# RSheet1.net
KiCad netlist of a schematic drawn in Altium Designer
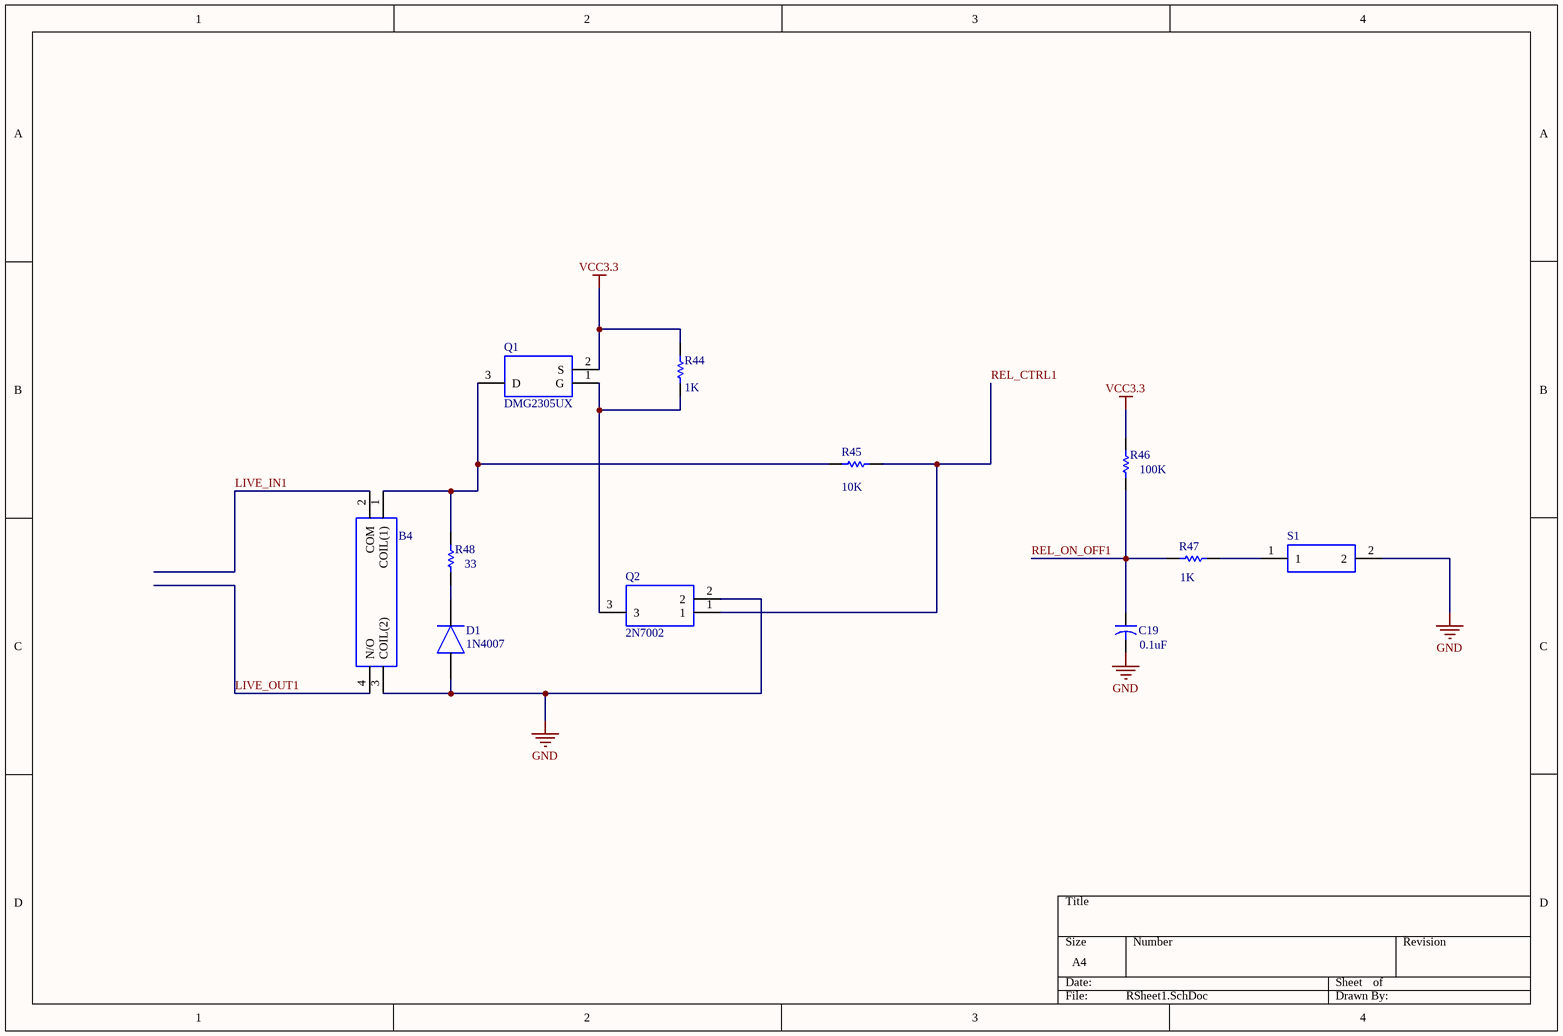
[diagram p0: RSheet1.SchDoc]

(export (version "E")
  (design (tool "Eeschema 10.0.6"))
  (components
    (comp (ref "B4")
      (value "HF3FA_005-HTF")
      (footprint "HF3FA005HTF:HF3FA005HTF")
      (description "Subminiature high power relay. 10A 5V.")
      (fields (field (name "MANUFACTURER_PART_NUMBER") "HF3FA/005-HTF"))
      (libsource (lib "HF3FA_005-HTF") (part "HF3FA_005-HTF"))
    )
    (comp (ref "C19")
      (value "0.1uF")
      (footprint "RESC0603X26N:RESC0603X26N")
      (description "Capacitor")
      (fields (field (name "Comment") "Cap2") (field (name "PUBLISHER") "Altium Limited"))
      (libsource (lib "Miscellaneous Devices") (part "Cap2"))
    )
    (comp (ref "D1")
      (value "1N4007")
      (footprint "DIOAD1408W86L464D236:DIOAD1408W86L464D236")
      (description "Diode Standard 1A 1000V 1Vf DO41 Diodes Inc 1N4007-T, Switching Diode, 1000V 1A, 2-Pin DO-41")
      (fields (field (name "RS PART NUMBER") "7384724P") (field (name "MANUFACTURER_PART_NUMBER") "1N4007-T"))
      (libsource (lib "1N4007-T") (part "1N4007-T"))
    )
    (comp (ref "Q1")
      (value "DMG2305UX")
      (footprint "SOT96P240X100-3N:SOT96P240X100-3N")
      (fields
        (field (name "RS PART NUMBER") "1219640")
        (field (name "MANUFACTURER_PART_NUMBER") "DMG2305UX-7")
      )
      (libsource (lib "DMG2305UX-7") (part "DMG2305UX-7"))
    )
    (comp (ref "Q2")
      (value "2N7002")
      (footprint "SOT95P230X110-3N:SOT95P230X110-3N")
      (fields
        (field (name "RS PART NUMBER") "1125526")
        (field (name "MANUFACTURER_PART_NUMBER") "2N7002,215")
      )
      (libsource (lib "2N7002_215") (part "2N7002_215"))
    )
    (comp (ref "R44")
      (value "1K")
      (footprint "AXIAL-0.3")
      (description "Resistor")
      (fields (field (name "Comment") "Res1") (field (name "PUBLISHER") "Altium Limited"))
      (libsource (lib "Miscellaneous Devices") (part "Res1"))
    )
    (comp (ref "R45")
      (value "10K")
      (footprint "AXIAL-0.3")
      (description "Resistor")
      (fields (field (name "Comment") "Res1") (field (name "PUBLISHER") "Altium Limited"))
      (libsource (lib "Miscellaneous Devices") (part "Res1"))
    )
    (comp (ref "R46")
      (value "100K")
      (footprint "RESC0603X26N:RESC0603X26N")
      (description "Resistor")
      (fields (field (name "Comment") "Res1") (field (name "PUBLISHER") "Altium Limited"))
      (libsource (lib "Miscellaneous Devices") (part "Res1"))
    )
    (comp (ref "R47")
      (value "1K")
      (footprint "RESC0603X26N:RESC0603X26N")
      (description "Resistor")
      (fields (field (name "Comment") "Res1") (field (name "PUBLISHER") "Altium Limited"))
      (libsource (lib "Miscellaneous Devices") (part "Res1"))
    )
    (comp (ref "R48")
      (value "33")
      (footprint "AXIAL-0.3")
      (description "Resistor")
      (fields (field (name "PUBLISHER") "Altium Limited"))
      (libsource (lib "Miscellaneous Devices") (part "Res1"))
    )
    (comp (ref "S1")
      (value "TL3330AF260QG")
      (footprint "SMD & J-Bend Tact Switch WS-TASV:434121043836")
      (description "Tactile Switches 50mA@12VDC 260g OF Silver contacts")
      (libsource (lib "TL3330AF260QG") (part "TL3330AF260QG"))
    )
  )
  (nets
    (net (code "1") (name "/LIVE_IN1") (class "Default")
      (node (ref "B4") (pin "2") (pinfunction "COM_2") (pintype "passive"))
    )
    (net (code "2") (name "/LIVE_OUT1") (class "Default")
      (node (ref "B4") (pin "4") (pinfunction "N/O_4") (pintype "passive"))
    )
    (net (code "3") (name "/REL_CTRL1") (class "Default")
      (node (ref "Q2") (pin "1") (pinfunction "1_1") (pintype "passive"))
      (node (ref "R45") (pin "2") (pinfunction "2_2") (pintype "passive"))
    )
    (net (code "4") (name "/REL_ON_OFF1") (class "Default")
      (node (ref "C19") (pin "1") (pinfunction "1_1") (pintype "passive"))
      (node (ref "R46") (pin "1") (pinfunction "1_1") (pintype "passive"))
      (node (ref "R47") (pin "1") (pinfunction "1_1") (pintype "passive"))
    )
    (net (code "5") (name "GND") (class "Default")
      (node (ref "B4") (pin "3") (pinfunction "COIL(2)_3") (pintype "passive"))
      (node (ref "C19") (pin "2") (pinfunction "2_2") (pintype "passive"))
      (node (ref "D1") (pin "2") (pinfunction "A_2") (pintype "passive"))
      (node (ref "Q2") (pin "2") (pinfunction "2_2") (pintype "passive"))
      (node (ref "S1") (pin "2") (pinfunction "2_2") (pintype "passive"))
    )
    (net (code "6") (name "Net-(B4-COIL(1))") (class "Default")
      (node (ref "B4") (pin "1") (pinfunction "COIL(1)_1") (pintype "passive"))
      (node (ref "Q1") (pin "3") (pinfunction "D_3") (pintype "passive"))
      (node (ref "R45") (pin "1") (pinfunction "1_1") (pintype "passive"))
      (node (ref "R48") (pin "2") (pinfunction "2_2") (pintype "passive"))
    )
    (net (code "7") (name "Net-(D1-K)") (class "Default")
      (node (ref "D1") (pin "1") (pinfunction "K_1") (pintype "passive"))
      (node (ref "R48") (pin "1") (pinfunction "1_1") (pintype "passive"))
    )
    (net (code "8") (name "Net-(Q1-G)") (class "Default")
      (node (ref "Q1") (pin "1") (pinfunction "G_1") (pintype "passive"))
      (node (ref "Q2") (pin "3") (pinfunction "3_3") (pintype "passive"))
      (node (ref "R44") (pin "1") (pinfunction "1_1") (pintype "passive"))
    )
    (net (code "9") (name "Net-(R47-Pad2)") (class "Default")
      (node (ref "R47") (pin "2") (pinfunction "2_2") (pintype "passive"))
      (node (ref "S1") (pin "1") (pinfunction "1_1") (pintype "passive"))
    )
    (net (code "10") (name "VCC3.3") (class "Default")
      (node (ref "Q1") (pin "2") (pinfunction "S_2") (pintype "passive"))
      (node (ref "R44") (pin "2") (pinfunction "2_2") (pintype "passive"))
      (node (ref "R46") (pin "2") (pinfunction "2_2") (pintype "passive"))
    )
  )
)
